# S7CAS-PLEIADES-CARTE-MERE_Pxx_IO_SENSOR.net
KiCad netlist of a schematic drawn in Altium Designer
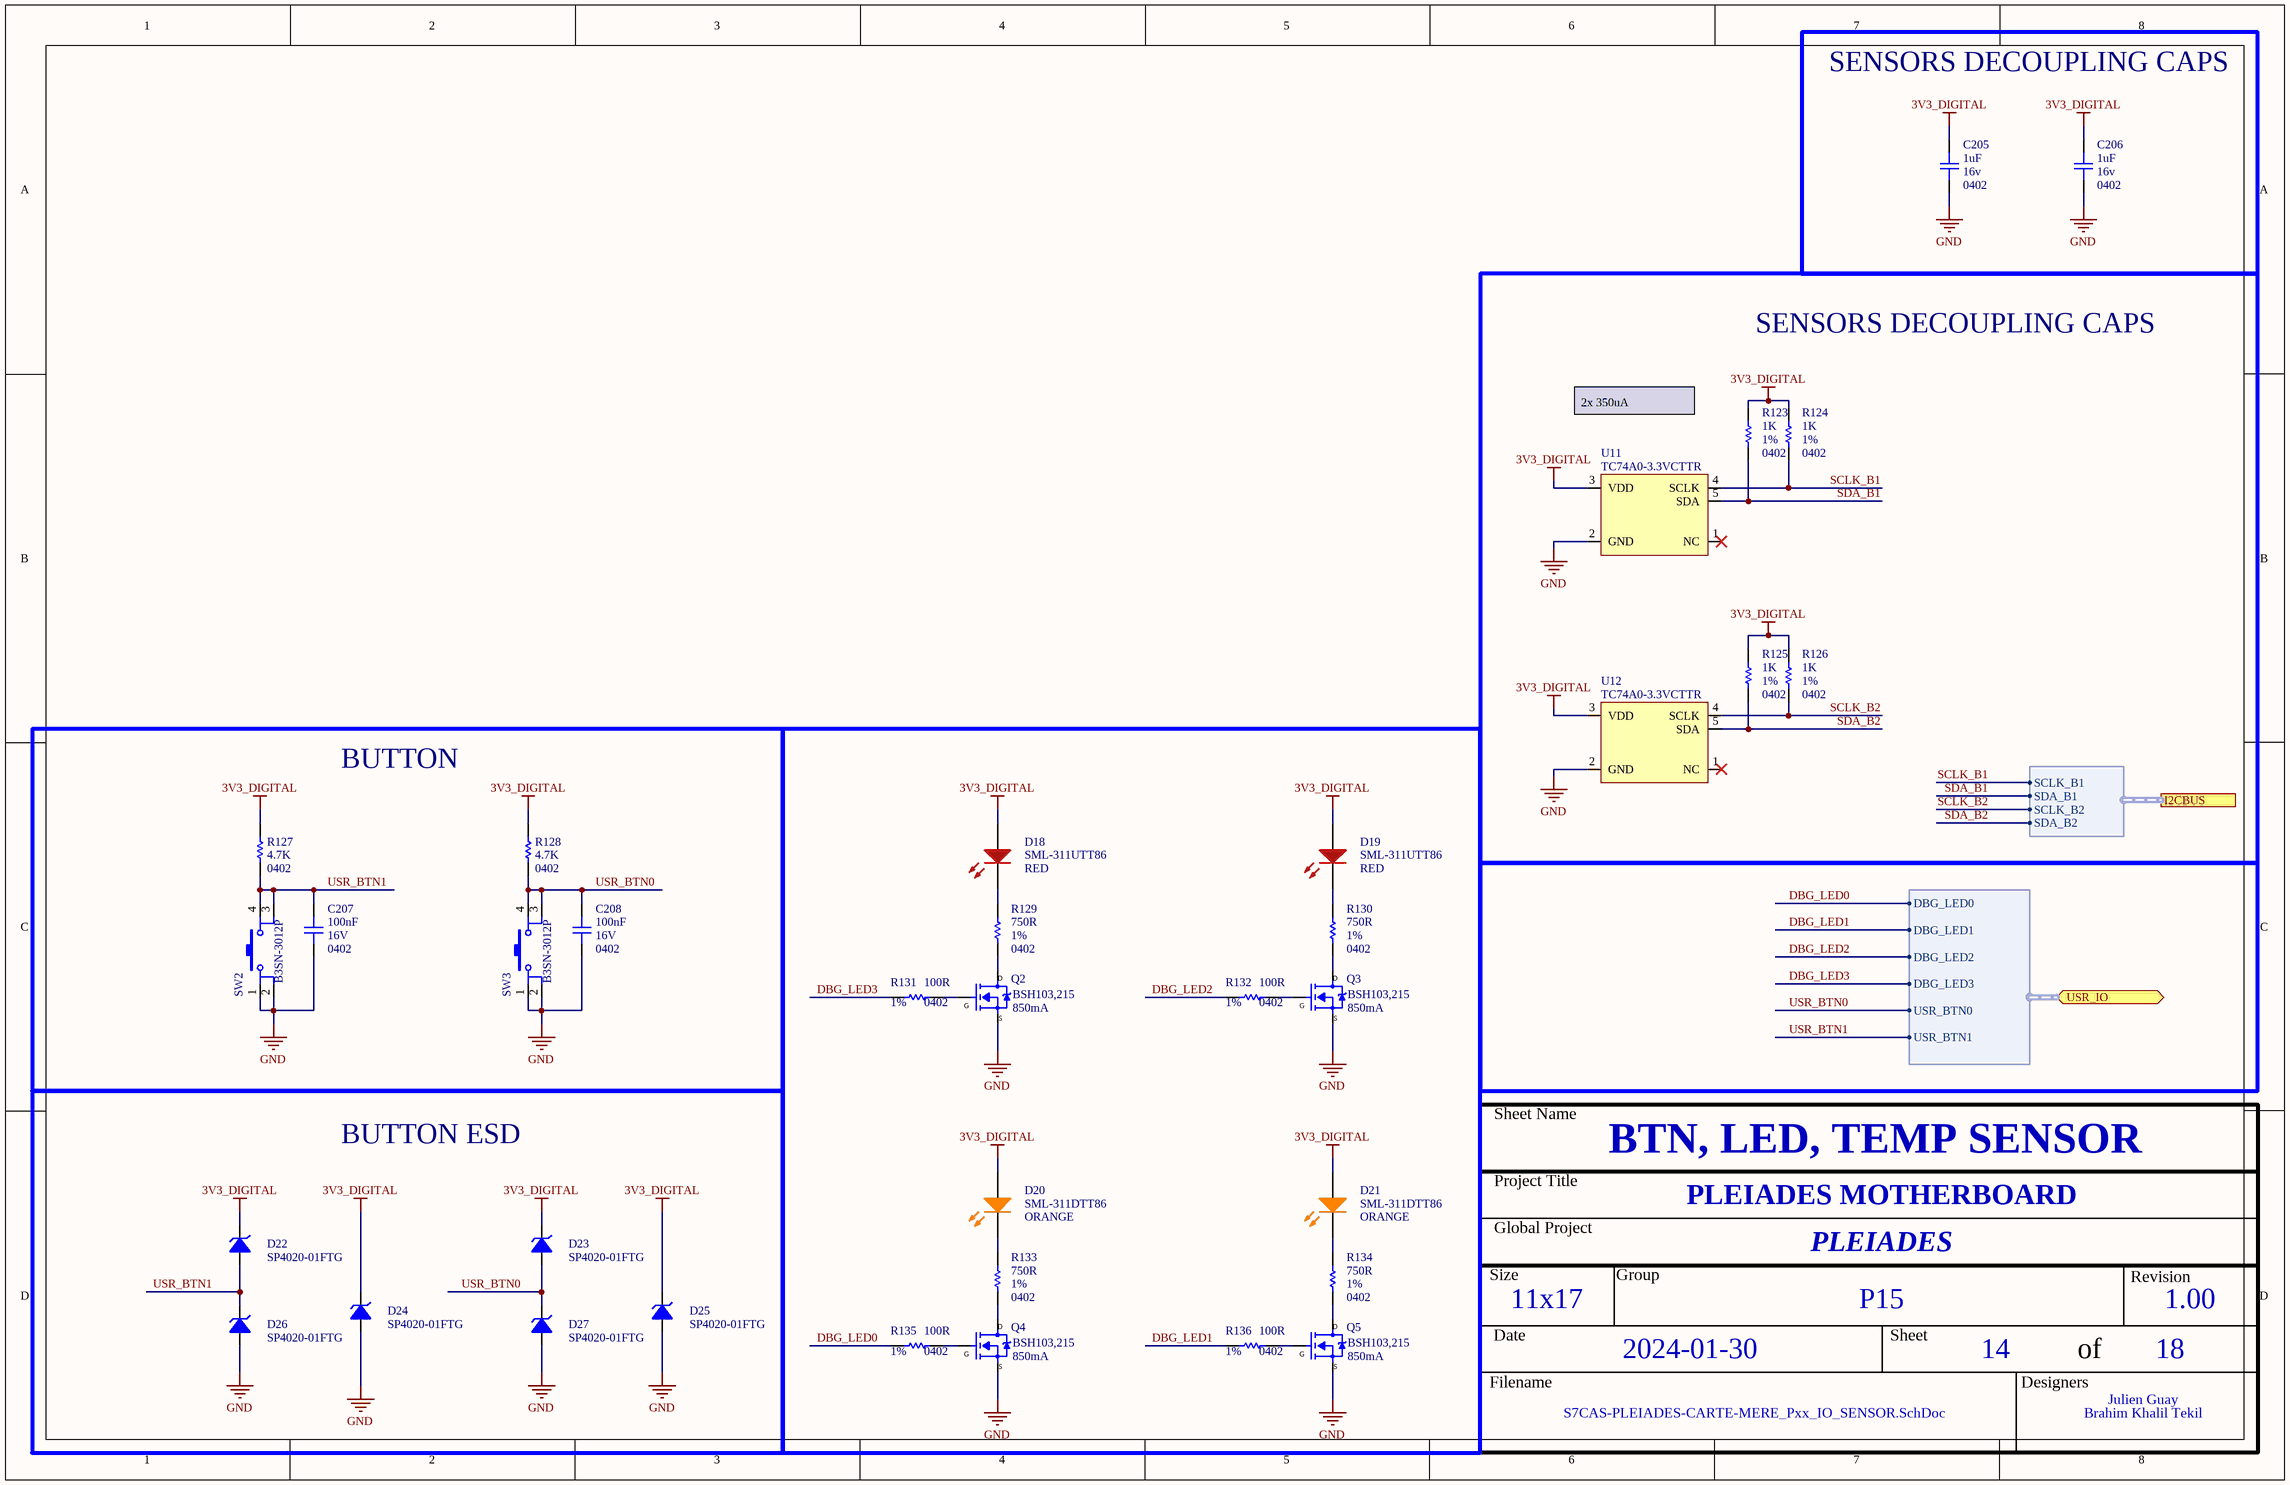
[diagram p0: S7CAS-PLEIADES-CARTE-MERE_Pxx_IO_SENSOR.SchDoc]

(export (version "E")
  (design (tool "Eeschema 10.0.6"))
  (components
    (comp (ref "C205")
      (value "1uF")
      (footprint "S7CAS_LIB2023:CAP_0402")
      (description "CAP - 0402")
      (fields
        (field (name "VOLTAGE") "16v")
        (field (name "PACKAGE") "0402")
        (field (name "Comment") "0402")
        (field (name "CREATEDBY") "Jonathan Bouchard")
      )
      (libsource (lib "S7CAS_LIB2023") (part "CAP - 0603"))
    )
    (comp (ref "C206")
      (value "1uF")
      (footprint "S7CAS_LIB2023:CAP_0402")
      (description "CAP - 0402")
      (fields
        (field (name "VOLTAGE") "16v")
        (field (name "PACKAGE") "0402")
        (field (name "Comment") "0402")
        (field (name "CREATEDBY") "Jonathan Bouchard")
      )
      (libsource (lib "S7CAS_LIB2023") (part "CAP - 0603"))
    )
    (comp (ref "C207")
      (value "100nF")
      (footprint "S7CAS_LIB2023:CAP_0402")
      (description "CAP - 0402")
      (fields
        (field (name "VOLTAGE") "16V")
        (field (name "PACKAGE") "0402")
        (field (name "Comment") "0402")
        (field (name "CREATEDBY") "Jonathan Bouchard")
      )
      (libsource (lib "S7CAS_LIB2023") (part "CAP - 0603"))
    )
    (comp (ref "C208")
      (value "100nF")
      (footprint "S7CAS_LIB2023:CAP_0402")
      (description "CAP - 0402")
      (fields
        (field (name "VOLTAGE") "16V")
        (field (name "PACKAGE") "0402")
        (field (name "Comment") "0402")
        (field (name "CREATEDBY") "Jonathan Bouchard")
      )
      (libsource (lib "S7CAS_LIB2023") (part "CAP - 0603"))
    )
    (comp (ref "D18")
      (value "SML-311UTT86")
      (footprint "LED_0603")
      (description "LED - 620nM RED 2mA - 0603")
      (fields
        (field (name "VOLTAGE") "1.8V")
        (field (name "MFG") "ROHM Semiconductor")
        (field (name "ALTIUM_VALUE") "RED")
        (field (name "CREATEDBY") "Jonathan Bouchard")
      )
      (libsource (lib "S7CAS_LIB2023") (part "LED_SML-311UTT86"))
    )
    (comp (ref "D19")
      (value "SML-311UTT86")
      (footprint "LED_0603")
      (description "LED - 620nM RED 2mA - 0603")
      (fields
        (field (name "VOLTAGE") "1.8V")
        (field (name "MFG") "ROHM Semiconductor")
        (field (name "ALTIUM_VALUE") "RED")
        (field (name "CREATEDBY") "Jonathan Bouchard")
      )
      (libsource (lib "S7CAS_LIB2023") (part "LED_SML-311UTT86"))
    )
    (comp (ref "D20")
      (value "SML-311DTT86")
      (footprint "LED_0603")
      (description "LED - 611nM ORANGE 2mA - 0603")
      (fields
        (field (name "VOLTAGE") "1.8V")
        (field (name "MFG") "ROHM Semiconductor")
        (field (name "ALTIUM_VALUE") "ORANGE")
        (field (name "CREATEDBY") "Jonathan Bouchard")
      )
      (libsource (lib "S7CAS_LIB2023") (part "LED_SML-311DTT86"))
    )
    (comp (ref "D21")
      (value "SML-311DTT86")
      (footprint "LED_0603")
      (description "LED - 611nM ORANGE 2mA - 0603")
      (fields
        (field (name "VOLTAGE") "1.8V")
        (field (name "MFG") "ROHM Semiconductor")
        (field (name "ALTIUM_VALUE") "ORANGE")
        (field (name "CREATEDBY") "Jonathan Bouchard")
      )
      (libsource (lib "S7CAS_LIB2023") (part "LED_SML-311DTT86"))
    )
    (comp (ref "D22")
      (value "SP4020-01FTG")
      (footprint "S7CAS_LIB2023:SOD323 - UNIDIR")
      (description "TVS - 3.3VWM 21.8V (Typ) Clamp 30A (8/20µs) Ipp Tvs Diode Surface Mount SOD-323")
      (libsource (lib "S7CAS_LIB2023") (part "TVS_SP4020-01FTG"))
    )
    (comp (ref "D23")
      (value "SP4020-01FTG")
      (footprint "S7CAS_LIB2023:SOD323 - UNIDIR")
      (description "TVS - 3.3VWM 21.8V (Typ) Clamp 30A (8/20µs) Ipp Tvs Diode Surface Mount SOD-323")
      (libsource (lib "S7CAS_LIB2023") (part "TVS_SP4020-01FTG"))
    )
    (comp (ref "D24")
      (value "SP4020-01FTG")
      (footprint "S7CAS_LIB2023:SOD323 - UNIDIR")
      (description "TVS - 3.3VWM 21.8V (Typ) Clamp 30A (8/20µs) Ipp Tvs Diode Surface Mount SOD-323")
      (libsource (lib "S7CAS_LIB2023") (part "TVS_SP4020-01FTG"))
    )
    (comp (ref "D25")
      (value "SP4020-01FTG")
      (footprint "S7CAS_LIB2023:SOD323 - UNIDIR")
      (description "TVS - 3.3VWM 21.8V (Typ) Clamp 30A (8/20µs) Ipp Tvs Diode Surface Mount SOD-323")
      (libsource (lib "S7CAS_LIB2023") (part "TVS_SP4020-01FTG"))
    )
    (comp (ref "D26")
      (value "SP4020-01FTG")
      (footprint "S7CAS_LIB2023:SOD323 - UNIDIR")
      (description "TVS - 3.3VWM 21.8V (Typ) Clamp 30A (8/20µs) Ipp Tvs Diode Surface Mount SOD-323")
      (libsource (lib "S7CAS_LIB2023") (part "TVS_SP4020-01FTG"))
    )
    (comp (ref "D27")
      (value "SP4020-01FTG")
      (footprint "S7CAS_LIB2023:SOD323 - UNIDIR")
      (description "TVS - 3.3VWM 21.8V (Typ) Clamp 30A (8/20µs) Ipp Tvs Diode Surface Mount SOD-323")
      (libsource (lib "S7CAS_LIB2023") (part "TVS_SP4020-01FTG"))
    )
    (comp (ref "Q2")
      (value "BSH103,215")
      (footprint "SOT23-3")
      (description "N-Channel  Enhancement Mode Field Effect Transistor")
      (fields (field (name "CURRENT") "850mA"))
      (libsource (lib "S7CAS_LIB2023") (part "MOS_N_CHANNEL"))
    )
    (comp (ref "Q3")
      (value "BSH103,215")
      (footprint "SOT23-3")
      (description "N-Channel  Enhancement Mode Field Effect Transistor")
      (fields (field (name "CURRENT") "850mA"))
      (libsource (lib "S7CAS_LIB2023") (part "MOS_N_CHANNEL"))
    )
    (comp (ref "Q4")
      (value "BSH103,215")
      (footprint "SOT23-3")
      (description "N-Channel  Enhancement Mode Field Effect Transistor")
      (fields (field (name "CURRENT") "850mA"))
      (libsource (lib "S7CAS_LIB2023") (part "MOS_N_CHANNEL"))
    )
    (comp (ref "Q5")
      (value "BSH103,215")
      (footprint "SOT23-3")
      (description "N-Channel  Enhancement Mode Field Effect Transistor")
      (fields (field (name "CURRENT") "850mA"))
      (libsource (lib "S7CAS_LIB2023") (part "MOS_N_CHANNEL"))
    )
    (comp (ref "R123")
      (value "1K")
      (footprint "S7CAS_LIB2023:RES_0402")
      (description "RES - 0402")
      (fields
        (field (name "PACKAGE") "0402")
        (field (name "PRECISION") "1%")
        (field (name "Comment") "RES - 0603")
        (field (name "CREATEDBY") "Jonathan Bouchard")
      )
      (libsource (lib "S7CAS_LIB2023") (part "RES - 0603"))
    )
    (comp (ref "R124")
      (value "1K")
      (footprint "S7CAS_LIB2023:RES_0402")
      (description "RES - 0402")
      (fields
        (field (name "PACKAGE") "0402")
        (field (name "PRECISION") "1%")
        (field (name "Comment") "RES - 0603")
        (field (name "CREATEDBY") "Jonathan Bouchard")
      )
      (libsource (lib "S7CAS_LIB2023") (part "RES - 0603"))
    )
    (comp (ref "R125")
      (value "1K")
      (footprint "S7CAS_LIB2023:RES_0402")
      (description "RES - 0402")
      (fields
        (field (name "PACKAGE") "0402")
        (field (name "PRECISION") "1%")
        (field (name "Comment") "RES - 0603")
        (field (name "CREATEDBY") "Jonathan Bouchard")
      )
      (libsource (lib "S7CAS_LIB2023") (part "RES - 0603"))
    )
    (comp (ref "R126")
      (value "1K")
      (footprint "S7CAS_LIB2023:RES_0402")
      (description "RES - 0402")
      (fields
        (field (name "PACKAGE") "0402")
        (field (name "PRECISION") "1%")
        (field (name "Comment") "RES - 0603")
        (field (name "CREATEDBY") "Jonathan Bouchard")
      )
      (libsource (lib "S7CAS_LIB2023") (part "RES - 0603"))
    )
    (comp (ref "R127")
      (value "4.7K")
      (footprint "S7CAS_LIB2023:RES_0402")
      (description "RES - 0402")
      (fields
        (field (name "PACKAGE") "0402")
        (field (name "Comment") "RES - 0603")
        (field (name "CREATEDBY") "Jonathan Bouchard")
      )
      (libsource (lib "S7CAS_LIB2023") (part "RES - 0603"))
    )
    (comp (ref "R128")
      (value "4.7K")
      (footprint "S7CAS_LIB2023:RES_0402")
      (description "RES - 0402")
      (fields
        (field (name "PACKAGE") "0402")
        (field (name "Comment") "RES - 0603")
        (field (name "CREATEDBY") "Jonathan Bouchard")
      )
      (libsource (lib "S7CAS_LIB2023") (part "RES - 0603"))
    )
    (comp (ref "R129")
      (value "750R")
      (footprint "S7CAS_LIB2023:RES_0402")
      (description "RES - 0402")
      (fields
        (field (name "PACKAGE") "0402")
        (field (name "PRECISION") "1%")
        (field (name "Comment") "RES - 0603")
        (field (name "CREATEDBY") "Jonathan Bouchard")
      )
      (libsource (lib "S7CAS_LIB2023") (part "RES - 0603"))
    )
    (comp (ref "R130")
      (value "750R")
      (footprint "S7CAS_LIB2023:RES_0402")
      (description "RES - 0402")
      (fields
        (field (name "PACKAGE") "0402")
        (field (name "PRECISION") "1%")
        (field (name "Comment") "RES - 0603")
        (field (name "CREATEDBY") "Jonathan Bouchard")
      )
      (libsource (lib "S7CAS_LIB2023") (part "RES - 0603"))
    )
    (comp (ref "R131")
      (value "100R")
      (footprint "S7CAS_LIB2023:RES_0402")
      (description "RES - 0402")
      (fields
        (field (name "PACKAGE") "0402")
        (field (name "PRECISION") "1%")
        (field (name "Comment") "RES - 0603")
        (field (name "CREATEDBY") "Jonathan Bouchard")
      )
      (libsource (lib "S7CAS_LIB2023") (part "RES - 0603"))
    )
    (comp (ref "R132")
      (value "100R")
      (footprint "S7CAS_LIB2023:RES_0402")
      (description "RES - 0402")
      (fields
        (field (name "PACKAGE") "0402")
        (field (name "PRECISION") "1%")
        (field (name "Comment") "RES - 0603")
        (field (name "CREATEDBY") "Jonathan Bouchard")
      )
      (libsource (lib "S7CAS_LIB2023") (part "RES - 0603"))
    )
    (comp (ref "R133")
      (value "750R")
      (footprint "S7CAS_LIB2023:RES_0402")
      (description "RES - 0402")
      (fields
        (field (name "PACKAGE") "0402")
        (field (name "PRECISION") "1%")
        (field (name "Comment") "RES - 0603")
        (field (name "CREATEDBY") "Jonathan Bouchard")
      )
      (libsource (lib "S7CAS_LIB2023") (part "RES - 0603"))
    )
    (comp (ref "R134")
      (value "750R")
      (footprint "S7CAS_LIB2023:RES_0402")
      (description "RES - 0402")
      (fields
        (field (name "PACKAGE") "0402")
        (field (name "PRECISION") "1%")
        (field (name "Comment") "RES - 0603")
        (field (name "CREATEDBY") "Jonathan Bouchard")
      )
      (libsource (lib "S7CAS_LIB2023") (part "RES - 0603"))
    )
    (comp (ref "R135")
      (value "100R")
      (footprint "S7CAS_LIB2023:RES_0402")
      (description "RES - 0402")
      (fields
        (field (name "PACKAGE") "0402")
        (field (name "PRECISION") "1%")
        (field (name "Comment") "RES - 0603")
        (field (name "CREATEDBY") "Jonathan Bouchard")
      )
      (libsource (lib "S7CAS_LIB2023") (part "RES - 0603"))
    )
    (comp (ref "R136")
      (value "100R")
      (footprint "S7CAS_LIB2023:RES_0402")
      (description "RES - 0402")
      (fields
        (field (name "PACKAGE") "0402")
        (field (name "PRECISION") "1%")
        (field (name "Comment") "RES - 0603")
        (field (name "CREATEDBY") "Jonathan Bouchard")
      )
      (libsource (lib "S7CAS_LIB2023") (part "RES - 0603"))
    )
    (comp (ref "SW2")
      (value "B3SN-3012P")
      (footprint "SWI_TACT_B3SN-3012P")
      (description "SWI - TACT SPST-NO 0.05A 24V - 4-SMD")
      (fields
        (field (name "MFG") "Omron")
        (field (name "VOLTAGE") "24V")
        (field (name "CREATEDBY") "Jonathan Bouchard")
      )
      (libsource (lib "S7CAS_LIB2023") (part "SWI_TACT_B3SN-3012P"))
    )
    (comp (ref "SW3")
      (value "B3SN-3012P")
      (footprint "SWI_TACT_B3SN-3012P")
      (description "SWI - TACT SPST-NO 0.05A 24V - 4-SMD")
      (fields
        (field (name "MFG") "Omron")
        (field (name "VOLTAGE") "24V")
        (field (name "CREATEDBY") "Jonathan Bouchard")
      )
      (libsource (lib "S7CAS_LIB2023") (part "SWI_TACT_B3SN-3012P"))
    )
    (comp (ref "U11")
      (value "TC74A0-3.3VCTTR")
      (footprint "SEN_TEMP_TC74A0-3.3VCTTR")
      (description "SENS - TEMPERATURE SENSOR I2C/SMBUS - SOT23-5")
      (fields
        (field (name "VOLTAGE") "2.7 V ~ 5.5 V")
        (field (name "MFG") "Microchip")
        (field (name "CREATEDBY") "Jonathan Bouchard")
      )
      (libsource (lib "S7CAS_LIB2023") (part "SENS_TEMP_TC74A0-3.3VCTTR"))
    )
    (comp (ref "U12")
      (value "TC74A0-3.3VCTTR")
      (footprint "SEN_TEMP_TC74A0-3.3VCTTR")
      (description "SENS - TEMPERATURE SENSOR I2C/SMBUS - SOT23-5")
      (fields
        (field (name "VOLTAGE") "2.7 V ~ 5.5 V")
        (field (name "MFG") "Microchip")
        (field (name "CREATEDBY") "Jonathan Bouchard")
      )
      (libsource (lib "S7CAS_LIB2023") (part "SENS_TEMP_TC74A0-3.3VCTTR"))
    )
  )
  (nets
    (net (code "3") (name "/DBG_LED0") (class "Default")
      (node (ref "R135") (pin "2") (pinfunction "2_2") (pintype "passive"))
    )
    (net (code "4") (name "/DBG_LED1") (class "Default")
      (node (ref "R136") (pin "2") (pinfunction "2_2") (pintype "passive"))
    )
    (net (code "5") (name "/DBG_LED2") (class "Default")
      (node (ref "R132") (pin "2") (pinfunction "2_2") (pintype "passive"))
    )
    (net (code "6") (name "/DBG_LED3") (class "Default")
      (node (ref "R131") (pin "2") (pinfunction "2_2") (pintype "passive"))
    )
    (net (code "7") (name "/SCLK_B1") (class "Default")
      (node (ref "R124") (pin "1") (pinfunction "1_1") (pintype "passive"))
      (node (ref "U11") (pin "4") (pinfunction "SCLK_4") (pintype "passive"))
    )
    (net (code "8") (name "/SCLK_B2") (class "Default")
      (node (ref "R126") (pin "1") (pinfunction "1_1") (pintype "passive"))
      (node (ref "U12") (pin "4") (pinfunction "SCLK_4") (pintype "passive"))
    )
    (net (code "9") (name "/SDA_B1") (class "Default")
      (node (ref "R123") (pin "1") (pinfunction "1_1") (pintype "passive"))
      (node (ref "U11") (pin "5") (pinfunction "SDA_5") (pintype "passive"))
    )
    (net (code "10") (name "/SDA_B2") (class "Default")
      (node (ref "R125") (pin "1") (pinfunction "1_1") (pintype "passive"))
      (node (ref "U12") (pin "5") (pinfunction "SDA_5") (pintype "passive"))
    )
    (net (code "11") (name "/USR_BTN0") (class "Default")
      (node (ref "C208") (pin "2") (pinfunction "2_2") (pintype "passive"))
      (node (ref "D23") (pin "2") (pinfunction "2_2") (pintype "passive"))
      (node (ref "D27") (pin "1") (pinfunction "1_1") (pintype "passive"))
      (node (ref "R128") (pin "1") (pinfunction "1_1") (pintype "passive"))
      (node (ref "SW3") (pin "3") (pinfunction "3_3") (pintype "passive"))
      (node (ref "SW3") (pin "4") (pinfunction "4_4") (pintype "passive"))
    )
    (net (code "12") (name "/USR_BTN1") (class "Default")
      (node (ref "C207") (pin "2") (pinfunction "2_2") (pintype "passive"))
      (node (ref "D22") (pin "2") (pinfunction "2_2") (pintype "passive"))
      (node (ref "D26") (pin "1") (pinfunction "1_1") (pintype "passive"))
      (node (ref "R127") (pin "1") (pinfunction "1_1") (pintype "passive"))
      (node (ref "SW2") (pin "3") (pinfunction "3_3") (pintype "passive"))
      (node (ref "SW2") (pin "4") (pinfunction "4_4") (pintype "passive"))
    )
    (net (code "15") (name "3V3_DIGITAL") (class "Default")
      (node (ref "C205") (pin "2") (pinfunction "2_2") (pintype "passive"))
      (node (ref "C206") (pin "2") (pinfunction "2_2") (pintype "passive"))
      (node (ref "D18") (pin "A") (pinfunction "A_A") (pintype "passive"))
      (node (ref "D19") (pin "A") (pinfunction "A_A") (pintype "passive"))
      (node (ref "D20") (pin "A") (pinfunction "A_A") (pintype "passive"))
      (node (ref "D21") (pin "A") (pinfunction "A_A") (pintype "passive"))
      (node (ref "D22") (pin "1") (pinfunction "1_1") (pintype "passive"))
      (node (ref "D23") (pin "1") (pinfunction "1_1") (pintype "passive"))
      (node (ref "D24") (pin "1") (pinfunction "1_1") (pintype "passive"))
      (node (ref "D25") (pin "1") (pinfunction "1_1") (pintype "passive"))
      (node (ref "R123") (pin "2") (pinfunction "2_2") (pintype "passive"))
      (node (ref "R124") (pin "2") (pinfunction "2_2") (pintype "passive"))
      (node (ref "R125") (pin "2") (pinfunction "2_2") (pintype "passive"))
      (node (ref "R126") (pin "2") (pinfunction "2_2") (pintype "passive"))
      (node (ref "R127") (pin "2") (pinfunction "2_2") (pintype "passive"))
      (node (ref "R128") (pin "2") (pinfunction "2_2") (pintype "passive"))
      (node (ref "U11") (pin "3") (pinfunction "VDD_3") (pintype "passive"))
      (node (ref "U12") (pin "3") (pinfunction "VDD_3") (pintype "passive"))
    )
    (net (code "16") (name "GND") (class "Default")
      (node (ref "C205") (pin "1") (pinfunction "1_1") (pintype "passive"))
      (node (ref "C206") (pin "1") (pinfunction "1_1") (pintype "passive"))
      (node (ref "C207") (pin "1") (pinfunction "1_1") (pintype "passive"))
      (node (ref "C208") (pin "1") (pinfunction "1_1") (pintype "passive"))
      (node (ref "D24") (pin "2") (pinfunction "2_2") (pintype "passive"))
      (node (ref "D25") (pin "2") (pinfunction "2_2") (pintype "passive"))
      (node (ref "D26") (pin "2") (pinfunction "2_2") (pintype "passive"))
      (node (ref "D27") (pin "2") (pinfunction "2_2") (pintype "passive"))
      (node (ref "Q2") (pin "2") (pintype "passive"))
      (node (ref "Q3") (pin "2") (pintype "passive"))
      (node (ref "Q4") (pin "2") (pintype "passive"))
      (node (ref "Q5") (pin "2") (pintype "passive"))
      (node (ref "SW2") (pin "1") (pinfunction "1_1") (pintype "passive"))
      (node (ref "SW2") (pin "2") (pinfunction "2_2") (pintype "passive"))
      (node (ref "SW3") (pin "1") (pinfunction "1_1") (pintype "passive"))
      (node (ref "SW3") (pin "2") (pinfunction "2_2") (pintype "passive"))
      (node (ref "U11") (pin "2") (pinfunction "GND_2") (pintype "passive"))
      (node (ref "U12") (pin "2") (pinfunction "GND_2") (pintype "passive"))
    )
    (net (code "17") (name "Net-(D18-PadK)") (class "Default")
      (node (ref "D18") (pin "K") (pinfunction "K_K") (pintype "passive"))
      (node (ref "R129") (pin "2") (pinfunction "2_2") (pintype "passive"))
    )
    (net (code "18") (name "Net-(D19-PadK)") (class "Default")
      (node (ref "D19") (pin "K") (pinfunction "K_K") (pintype "passive"))
      (node (ref "R130") (pin "2") (pinfunction "2_2") (pintype "passive"))
    )
    (net (code "19") (name "Net-(D20-PadK)") (class "Default")
      (node (ref "D20") (pin "K") (pinfunction "K_K") (pintype "passive"))
      (node (ref "R133") (pin "2") (pinfunction "2_2") (pintype "passive"))
    )
    (net (code "20") (name "Net-(D21-PadK)") (class "Default")
      (node (ref "D21") (pin "K") (pinfunction "K_K") (pintype "passive"))
      (node (ref "R134") (pin "2") (pinfunction "2_2") (pintype "passive"))
    )
    (net (code "21") (name "Net-(Q2-Pad1)") (class "Default")
      (node (ref "Q2") (pin "1") (pintype "passive"))
      (node (ref "R131") (pin "1") (pinfunction "1_1") (pintype "passive"))
    )
    (net (code "22") (name "Net-(Q2-Pad3)") (class "Default")
      (node (ref "Q2") (pin "3") (pintype "passive"))
      (node (ref "R129") (pin "1") (pinfunction "1_1") (pintype "passive"))
    )
    (net (code "23") (name "Net-(Q3-Pad1)") (class "Default")
      (node (ref "Q3") (pin "1") (pintype "passive"))
      (node (ref "R132") (pin "1") (pinfunction "1_1") (pintype "passive"))
    )
    (net (code "24") (name "Net-(Q3-Pad3)") (class "Default")
      (node (ref "Q3") (pin "3") (pintype "passive"))
      (node (ref "R130") (pin "1") (pinfunction "1_1") (pintype "passive"))
    )
    (net (code "25") (name "Net-(Q4-Pad1)") (class "Default")
      (node (ref "Q4") (pin "1") (pintype "passive"))
      (node (ref "R135") (pin "1") (pinfunction "1_1") (pintype "passive"))
    )
    (net (code "26") (name "Net-(Q4-Pad3)") (class "Default")
      (node (ref "Q4") (pin "3") (pintype "passive"))
      (node (ref "R133") (pin "1") (pinfunction "1_1") (pintype "passive"))
    )
    (net (code "27") (name "Net-(Q5-Pad1)") (class "Default")
      (node (ref "Q5") (pin "1") (pintype "passive"))
      (node (ref "R136") (pin "1") (pinfunction "1_1") (pintype "passive"))
    )
    (net (code "28") (name "Net-(Q5-Pad3)") (class "Default")
      (node (ref "Q5") (pin "3") (pintype "passive"))
      (node (ref "R134") (pin "1") (pinfunction "1_1") (pintype "passive"))
    )
    (net (code "29") (name "unconnected-(U11-NC-Pad1)") (class "Default")
      (node (ref "U11") (pin "1") (pinfunction "NC_1") (pintype "passive+no_connect"))
    )
    (net (code "30") (name "unconnected-(U12-NC-Pad1)") (class "Default")
      (node (ref "U12") (pin "1") (pinfunction "NC_1") (pintype "passive+no_connect"))
    )
  )
)
